# HF_Control.net
KiCad netlist of a schematic drawn in Altium Designer
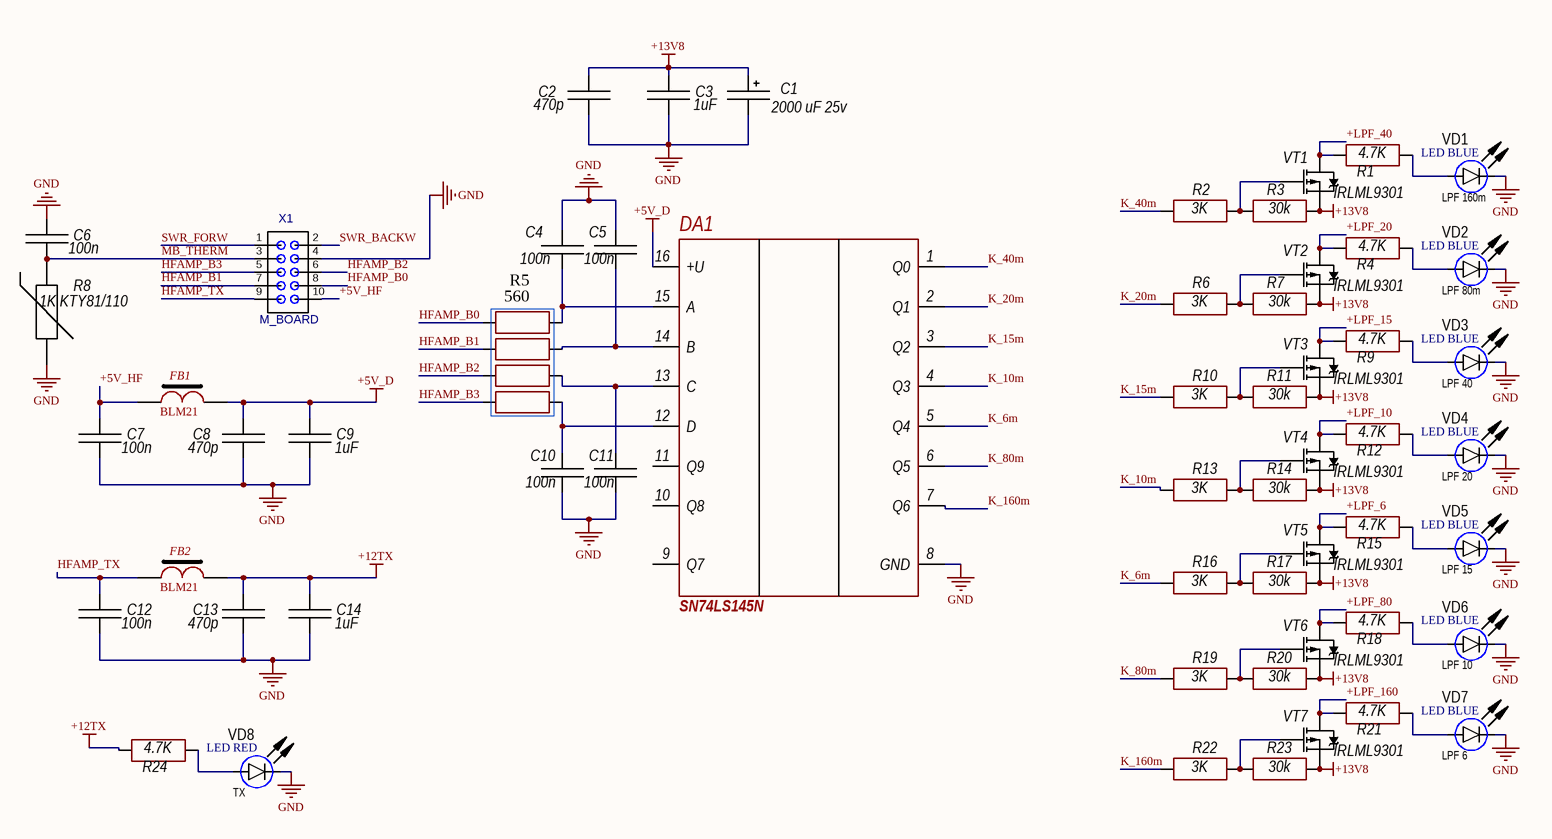
[diagram p0: HF_Control.SchDoc]

(export (version "E")
  (design (tool "Eeschema 10.0.6"))
  (components
    (comp (ref "C1")
      (value "2000 uF 25v")
      (footprint "standard:D13C5H20")
      (libsource (lib "Discrete") (part "AlumCap"))
    )
    (comp (ref "C2")
      (value "470p")
      (footprint "standard:CH0805C")
      (libsource (lib "Discrete") (part "Capacitor"))
    )
    (comp (ref "C3")
      (value "1uF")
      (footprint "standard:CH0805C")
      (libsource (lib "Discrete") (part "Capacitor"))
    )
    (comp (ref "C4")
      (value "100n")
      (footprint "standard:CH0805C")
      (libsource (lib "Discrete") (part "Capacitor"))
    )
    (comp (ref "C5")
      (value "100n")
      (footprint "standard:CH0805C")
      (libsource (lib "Discrete") (part "Capacitor"))
    )
    (comp (ref "C6")
      (value "100n")
      (footprint "standard:CH0805C")
      (libsource (lib "Discrete") (part "Capacitor"))
    )
    (comp (ref "C7")
      (value "100n")
      (footprint "standard:CH0805C")
      (libsource (lib "Discrete") (part "Capacitor"))
    )
    (comp (ref "C8")
      (value "470p")
      (footprint "standard:CH0805C")
      (libsource (lib "Discrete") (part "Capacitor"))
    )
    (comp (ref "C9")
      (value "1uF")
      (footprint "standard:CH0805C")
      (libsource (lib "Discrete") (part "Capacitor"))
    )
    (comp (ref "C10")
      (value "100n")
      (footprint "standard:CH0805C")
      (libsource (lib "Discrete") (part "Capacitor"))
    )
    (comp (ref "C11")
      (value "100n")
      (footprint "standard:CH0805C")
      (libsource (lib "Discrete") (part "Capacitor"))
    )
    (comp (ref "C12")
      (value "100n")
      (footprint "standard:CH0805C")
      (libsource (lib "Discrete") (part "Capacitor"))
    )
    (comp (ref "C13")
      (value "470p")
      (footprint "standard:CH0805C")
      (libsource (lib "Discrete") (part "Capacitor"))
    )
    (comp (ref "C14")
      (value "1uF")
      (footprint "standard:CH0805C")
      (libsource (lib "Discrete") (part "Capacitor"))
    )
    (comp (ref "DA1")
      (value "SN74LS145N")
      (footprint "16-SOP")
      (libsource (lib "Digital") (part "SN74LS145N"))
    )
    (comp (ref "FB1") (value "BLM21") (footprint "CH0805L") (libsource (lib "Discrete") (part "FB-1")))
    (comp (ref "FB2") (value "BLM21") (footprint "CH0805L") (libsource (lib "Discrete") (part "FB-1")))
    (comp (ref "R1")
      (value "4.7K")
      (footprint "standard:CH0805R")
      (libsource (lib "Discrete") (part "Resistor"))
    )
    (comp (ref "R2") (value "3K") (footprint "standard:CH0805R") (libsource (lib "") (part "Resistor_1")))
    (comp (ref "R3")
      (value "30k")
      (footprint "standard:CH0805R")
      (libsource (lib "Discrete") (part "Resistor"))
    )
    (comp (ref "R4")
      (value "4.7K")
      (footprint "standard:CH0805R")
      (libsource (lib "Discrete") (part "Resistor"))
    )
    (comp (ref "R5") (value "560") (footprint "CAT16") (libsource (lib "Discrete") (part "CAT10-0804")))
    (comp (ref "R6") (value "3K") (footprint "standard:CH0805R") (libsource (lib "") (part "Resistor_1")))
    (comp (ref "R7")
      (value "30k")
      (footprint "standard:CH0805R")
      (libsource (lib "Discrete") (part "Resistor"))
    )
    (comp (ref "R8")
      (value "1K KTY81/110")
      (footprint "CON: PBS-2")
      (libsource (lib "Discrete") (part "NTC"))
    )
    (comp (ref "R9")
      (value "4.7K")
      (footprint "standard:CH0805R")
      (libsource (lib "Discrete") (part "Resistor"))
    )
    (comp (ref "R10") (value "3K") (footprint "standard:CH0805R") (libsource (lib "") (part "Resistor_1")))
    (comp (ref "R11")
      (value "30k")
      (footprint "standard:CH0805R")
      (libsource (lib "Discrete") (part "Resistor"))
    )
    (comp (ref "R12")
      (value "4.7K")
      (footprint "standard:CH0805R")
      (libsource (lib "Discrete") (part "Resistor"))
    )
    (comp (ref "R13") (value "3K") (footprint "standard:CH0805R") (libsource (lib "") (part "Resistor_1")))
    (comp (ref "R14")
      (value "30k")
      (footprint "standard:CH0805R")
      (libsource (lib "Discrete") (part "Resistor"))
    )
    (comp (ref "R15")
      (value "4.7K")
      (footprint "standard:CH0805R")
      (libsource (lib "Discrete") (part "Resistor"))
    )
    (comp (ref "R16") (value "3K") (footprint "standard:CH0805R") (libsource (lib "") (part "Resistor_1")))
    (comp (ref "R17")
      (value "30k")
      (footprint "standard:CH0805R")
      (libsource (lib "Discrete") (part "Resistor"))
    )
    (comp (ref "R18")
      (value "4.7K")
      (footprint "standard:CH0805R")
      (libsource (lib "Discrete") (part "Resistor"))
    )
    (comp (ref "R19") (value "3K") (footprint "standard:CH0805R") (libsource (lib "") (part "Resistor_1")))
    (comp (ref "R20")
      (value "30k")
      (footprint "standard:CH0805R")
      (libsource (lib "Discrete") (part "Resistor"))
    )
    (comp (ref "R21")
      (value "4.7K")
      (footprint "standard:CH0805R")
      (libsource (lib "Discrete") (part "Resistor"))
    )
    (comp (ref "R22") (value "3K") (footprint "standard:CH0805R") (libsource (lib "") (part "Resistor_1")))
    (comp (ref "R23")
      (value "30k")
      (footprint "standard:CH0805R")
      (libsource (lib "Discrete") (part "Resistor"))
    )
    (comp (ref "R24")
      (value "4.7K")
      (footprint "standard:CH0805R")
      (libsource (lib "Discrete") (part "Resistor"))
    )
    (comp (ref "VD1")
      (value "LED BLUE")
      (footprint "StandardCase:LED: 0805B")
      (fields
        (field (name "VALUEMANUFACTURERPARTNUMBER") "LED, *, *, *, -55...+150°C")
        (field (name "COLOR") "LPF 160m")
      )
      (libsource (lib "Diode") (part "LED_single"))
    )
    (comp (ref "VD2")
      (value "LED BLUE")
      (footprint "StandardCase:LED: 0805B")
      (fields
        (field (name "VALUEMANUFACTURERPARTNUMBER") "LED, *, *, *, -55...+150°C")
        (field (name "COLOR") "LPF 80m")
      )
      (libsource (lib "Diode") (part "LED_single"))
    )
    (comp (ref "VD3")
      (value "LED BLUE")
      (footprint "StandardCase:LED: 0805B")
      (fields
        (field (name "VALUEMANUFACTURERPARTNUMBER") "LED, *, *, *, -55...+150°C")
        (field (name "COLOR") "LPF 40")
      )
      (libsource (lib "Diode") (part "LED_single"))
    )
    (comp (ref "VD4")
      (value "LED BLUE")
      (footprint "StandardCase:LED: 0805B")
      (fields
        (field (name "VALUEMANUFACTURERPARTNUMBER") "LED, *, *, *, -55...+150°C")
        (field (name "COLOR") "LPF 20")
      )
      (libsource (lib "Diode") (part "LED_single"))
    )
    (comp (ref "VD5")
      (value "LED BLUE")
      (footprint "StandardCase:LED: 0805B")
      (fields
        (field (name "VALUEMANUFACTURERPARTNUMBER") "LED, *, *, *, -55...+150°C")
        (field (name "COLOR") "LPF 15")
      )
      (libsource (lib "Diode") (part "LED_single"))
    )
    (comp (ref "VD6")
      (value "LED BLUE")
      (footprint "StandardCase:LED: 0805B")
      (fields
        (field (name "VALUEMANUFACTURERPARTNUMBER") "LED, *, *, *, -55...+150°C")
        (field (name "COLOR") "LPF 10")
      )
      (libsource (lib "Diode") (part "LED_single"))
    )
    (comp (ref "VD7")
      (value "LED BLUE")
      (footprint "StandardCase:LED: 0805B")
      (fields
        (field (name "VALUEMANUFACTURERPARTNUMBER") "LED, *, *, *, -55...+150°C")
        (field (name "COLOR") "LPF 6")
      )
      (libsource (lib "Diode") (part "LED_single"))
    )
    (comp (ref "VD8")
      (value "LED RED")
      (footprint "StandardCase:LED: 0805R")
      (fields
        (field (name "VALUEMANUFACTURERPARTNUMBER") "LED, *, *, *, -55...+150°C")
        (field (name "COLOR") "TX")
      )
      (libsource (lib "Diode") (part "LED_single"))
    )
    (comp (ref "VT1")
      (value "IRLML9301")
      (footprint "standard:SOT23_132")
      (description "Mosfet")
      (libsource (lib "Transistor") (part "IRLML9301"))
    )
    (comp (ref "VT2")
      (value "IRLML9301")
      (footprint "standard:SOT23_132")
      (description "Mosfet")
      (libsource (lib "Transistor") (part "IRLML9301"))
    )
    (comp (ref "VT3")
      (value "IRLML9301")
      (footprint "standard:SOT23_132")
      (description "Mosfet")
      (libsource (lib "Transistor") (part "IRLML9301"))
    )
    (comp (ref "VT4")
      (value "IRLML9301")
      (footprint "standard:SOT23_132")
      (description "Mosfet")
      (libsource (lib "Transistor") (part "IRLML9301"))
    )
    (comp (ref "VT5")
      (value "IRLML9301")
      (footprint "standard:SOT23_132")
      (description "Mosfet")
      (libsource (lib "Transistor") (part "IRLML9301"))
    )
    (comp (ref "VT6")
      (value "IRLML9301")
      (footprint "standard:SOT23_132")
      (description "Mosfet")
      (libsource (lib "Transistor") (part "IRLML9301"))
    )
    (comp (ref "VT7")
      (value "IRLML9301")
      (footprint "standard:SOT23_132")
      (description "Mosfet")
      (libsource (lib "Transistor") (part "IRLML9301"))
    )
    (comp (ref "X1")
      (value "M_BOARD")
      (footprint "CON: BH-10")
      (description "2*5 Pin")
      (libsource (lib "*") (part "IDC10"))
    )
  )
  (nets
    (net (code "1") (name "+5V_D") (class "Default")
      (node (ref "C8") (pin "1") (pinfunction "1_1") (pintype "power_in"))
      (node (ref "C9") (pin "1") (pinfunction "1_1") (pintype "power_in"))
      (node (ref "DA1") (pin "16") (pinfunction "+U_16") (pintype "passive"))
      (node (ref "FB1") (pin "1") (pinfunction "1_1") (pintype "passive"))
    )
    (net (code "2") (name "+12TX") (class "Default")
      (node (ref "C13") (pin "1") (pinfunction "1_1") (pintype "power_in"))
      (node (ref "C14") (pin "1") (pinfunction "1_1") (pintype "power_in"))
      (node (ref "FB2") (pin "1") (pinfunction "1_1") (pintype "passive"))
      (node (ref "R24") (pin "2") (pinfunction "2_2") (pintype "passive"))
    )
    (net (code "3") (name "+13V8") (class "Default")
      (node (ref "C1") (pin "1") (pinfunction "1_1") (pintype "power_in"))
      (node (ref "C2") (pin "1") (pinfunction "1_1") (pintype "power_in"))
      (node (ref "C3") (pin "1") (pinfunction "1_1") (pintype "power_in"))
      (node (ref "R11") (pin "1") (pinfunction "1_1") (pintype "passive"))
      (node (ref "R14") (pin "1") (pinfunction "1_1") (pintype "passive"))
      (node (ref "R17") (pin "1") (pinfunction "1_1") (pintype "passive"))
      (node (ref "R20") (pin "1") (pinfunction "1_1") (pintype "passive"))
      (node (ref "R23") (pin "1") (pinfunction "1_1") (pintype "passive"))
      (node (ref "R3") (pin "1") (pinfunction "1_1") (pintype "passive"))
      (node (ref "R7") (pin "1") (pinfunction "1_1") (pintype "passive"))
      (node (ref "VT1") (pin "2") (pinfunction "S_2") (pintype "passive"))
      (node (ref "VT2") (pin "2") (pinfunction "S_2") (pintype "passive"))
      (node (ref "VT3") (pin "2") (pinfunction "S_2") (pintype "passive"))
      (node (ref "VT4") (pin "2") (pinfunction "S_2") (pintype "passive"))
      (node (ref "VT5") (pin "2") (pinfunction "S_2") (pintype "passive"))
      (node (ref "VT6") (pin "2") (pinfunction "S_2") (pintype "passive"))
      (node (ref "VT7") (pin "2") (pinfunction "S_2") (pintype "passive"))
    )
    (net (code "4") (name "/+5V_HF") (class "Default")
      (node (ref "C7") (pin "1") (pinfunction "1_1") (pintype "power_in"))
      (node (ref "FB1") (pin "2") (pinfunction "2_2") (pintype "passive"))
      (node (ref "X1") (pin "10") (pinfunction "10_10") (pintype "passive"))
    )
    (net (code "5") (name "/+LPF_6") (class "Default")
      (node (ref "R15") (pin "2") (pinfunction "2_2") (pintype "passive"))
      (node (ref "VT5") (pin "3") (pinfunction "D_3") (pintype "passive"))
    )
    (net (code "6") (name "/+LPF_10") (class "Default")
      (node (ref "R12") (pin "2") (pinfunction "2_2") (pintype "passive"))
      (node (ref "VT4") (pin "3") (pinfunction "D_3") (pintype "passive"))
    )
    (net (code "7") (name "/+LPF_15") (class "Default")
      (node (ref "R9") (pin "2") (pinfunction "2_2") (pintype "passive"))
      (node (ref "VT3") (pin "3") (pinfunction "D_3") (pintype "passive"))
    )
    (net (code "8") (name "/+LPF_20") (class "Default")
      (node (ref "R4") (pin "2") (pinfunction "2_2") (pintype "passive"))
      (node (ref "VT2") (pin "3") (pinfunction "D_3") (pintype "passive"))
    )
    (net (code "9") (name "/+LPF_40") (class "Default")
      (node (ref "R1") (pin "2") (pinfunction "2_2") (pintype "passive"))
      (node (ref "VT1") (pin "3") (pinfunction "D_3") (pintype "passive"))
    )
    (net (code "10") (name "/+LPF_80") (class "Default")
      (node (ref "R18") (pin "2") (pinfunction "2_2") (pintype "passive"))
      (node (ref "VT6") (pin "3") (pinfunction "D_3") (pintype "passive"))
    )
    (net (code "11") (name "/+LPF_160") (class "Default")
      (node (ref "R21") (pin "2") (pinfunction "2_2") (pintype "passive"))
      (node (ref "VT7") (pin "3") (pinfunction "D_3") (pintype "passive"))
    )
    (net (code "12") (name "/HFAMP_B0") (class "Default")
      (node (ref "R5") (pin "1") (pinfunction "1_1") (pintype "passive"))
      (node (ref "X1") (pin "8") (pinfunction "8_8") (pintype "passive"))
    )
    (net (code "13") (name "/HFAMP_B1") (class "Default")
      (node (ref "R5") (pin "2") (pinfunction "2_2") (pintype "passive"))
      (node (ref "X1") (pin "7") (pinfunction "7_7") (pintype "passive"))
    )
    (net (code "14") (name "/HFAMP_B2") (class "Default")
      (node (ref "R5") (pin "3") (pinfunction "3_3") (pintype "passive"))
      (node (ref "X1") (pin "6") (pinfunction "6_6") (pintype "passive"))
    )
    (net (code "15") (name "/HFAMP_B3") (class "Default")
      (node (ref "R5") (pin "4") (pinfunction "4_4") (pintype "passive"))
      (node (ref "X1") (pin "5") (pinfunction "5_5") (pintype "passive"))
    )
    (net (code "16") (name "/HFAMP_TX") (class "Default")
      (node (ref "C12") (pin "1") (pinfunction "1_1") (pintype "power_in"))
      (node (ref "FB2") (pin "2") (pinfunction "2_2") (pintype "passive"))
      (node (ref "X1") (pin "9") (pinfunction "9_9") (pintype "passive"))
    )
    (net (code "17") (name "/K_6m") (class "Default")
      (node (ref "DA1") (pin "5") (pinfunction "Q4_5") (pintype "passive"))
      (node (ref "R16") (pin "2") (pinfunction "2_2") (pintype "passive"))
    )
    (net (code "18") (name "/K_10m") (class "Default")
      (node (ref "DA1") (pin "4") (pinfunction "Q3_4") (pintype "passive"))
      (node (ref "R13") (pin "2") (pinfunction "2_2") (pintype "passive"))
    )
    (net (code "19") (name "/K_15m") (class "Default")
      (node (ref "DA1") (pin "3") (pinfunction "Q2_3") (pintype "passive"))
      (node (ref "R10") (pin "2") (pinfunction "2_2") (pintype "passive"))
    )
    (net (code "20") (name "/K_20m") (class "Default")
      (node (ref "DA1") (pin "2") (pinfunction "Q1_2") (pintype "passive"))
      (node (ref "R6") (pin "2") (pinfunction "2_2") (pintype "passive"))
    )
    (net (code "21") (name "/K_40m") (class "Default")
      (node (ref "DA1") (pin "1") (pinfunction "Q0_1") (pintype "passive"))
      (node (ref "R2") (pin "2") (pinfunction "2_2") (pintype "passive"))
    )
    (net (code "22") (name "/K_80m") (class "Default")
      (node (ref "DA1") (pin "6") (pinfunction "Q5_6") (pintype "passive"))
      (node (ref "R19") (pin "2") (pinfunction "2_2") (pintype "passive"))
    )
    (net (code "23") (name "/K_160m") (class "Default")
      (node (ref "DA1") (pin "7") (pinfunction "Q6_7") (pintype "passive"))
      (node (ref "R22") (pin "2") (pinfunction "2_2") (pintype "passive"))
    )
    (net (code "24") (name "/MB_THERM") (class "Default")
      (node (ref "C6") (pin "2") (pinfunction "2_2") (pintype "power_in"))
      (node (ref "R8") (pin "2") (pinfunction "2_2") (pintype "passive"))
      (node (ref "X1") (pin "3") (pinfunction "3_3") (pintype "passive"))
    )
    (net (code "25") (name "/SWR_BACKW") (class "Default")
      (node (ref "X1") (pin "2") (pinfunction "2_2") (pintype "passive"))
    )
    (net (code "26") (name "/SWR_FORW") (class "Default")
      (node (ref "X1") (pin "1") (pinfunction "1_1") (pintype "passive"))
    )
    (net (code "27") (name "GND") (class "Default")
      (node (ref "C1") (pin "2") (pinfunction "2_2") (pintype "power_in"))
      (node (ref "C10") (pin "2") (pinfunction "2_2") (pintype "power_in"))
      (node (ref "C11") (pin "2") (pinfunction "2_2") (pintype "power_in"))
      (node (ref "C12") (pin "2") (pinfunction "2_2") (pintype "power_in"))
      (node (ref "C13") (pin "2") (pinfunction "2_2") (pintype "power_in"))
      (node (ref "C14") (pin "2") (pinfunction "2_2") (pintype "power_in"))
      (node (ref "C2") (pin "2") (pinfunction "2_2") (pintype "power_in"))
      (node (ref "C3") (pin "2") (pinfunction "2_2") (pintype "power_in"))
      (node (ref "C4") (pin "1") (pinfunction "1_1") (pintype "power_in"))
      (node (ref "C5") (pin "1") (pinfunction "1_1") (pintype "power_in"))
      (node (ref "C6") (pin "1") (pinfunction "1_1") (pintype "power_in"))
      (node (ref "C7") (pin "2") (pinfunction "2_2") (pintype "power_in"))
      (node (ref "C8") (pin "2") (pinfunction "2_2") (pintype "power_in"))
      (node (ref "C9") (pin "2") (pinfunction "2_2") (pintype "power_in"))
      (node (ref "DA1") (pin "8") (pinfunction "GND_8") (pintype "passive"))
      (node (ref "R8") (pin "1") (pinfunction "1_1") (pintype "passive"))
      (node (ref "VD1") (pin "2") (pinfunction "C_2") (pintype "passive"))
      (node (ref "VD2") (pin "2") (pinfunction "C_2") (pintype "passive"))
      (node (ref "VD3") (pin "2") (pinfunction "C_2") (pintype "passive"))
      (node (ref "VD4") (pin "2") (pinfunction "C_2") (pintype "passive"))
      (node (ref "VD5") (pin "2") (pinfunction "C_2") (pintype "passive"))
      (node (ref "VD6") (pin "2") (pinfunction "C_2") (pintype "passive"))
      (node (ref "VD7") (pin "2") (pinfunction "C_2") (pintype "passive"))
      (node (ref "VD8") (pin "2") (pinfunction "C_2") (pintype "passive"))
      (node (ref "X1") (pin "4") (pinfunction "4_4") (pintype "passive"))
    )
    (net (code "28") (name "Net-(DA1-A)") (class "Default")
      (node (ref "C4") (pin "2") (pinfunction "2_2") (pintype "power_in"))
      (node (ref "DA1") (pin "15") (pinfunction "A_15") (pintype "passive"))
      (node (ref "R5") (pin "5") (pinfunction "5_5") (pintype "passive"))
    )
    (net (code "29") (name "Net-(DA1-B)") (class "Default")
      (node (ref "C5") (pin "2") (pinfunction "2_2") (pintype "power_in"))
      (node (ref "DA1") (pin "14") (pinfunction "B_14") (pintype "passive"))
      (node (ref "R5") (pin "6") (pinfunction "6_6") (pintype "passive"))
    )
    (net (code "30") (name "Net-(DA1-C)") (class "Default")
      (node (ref "C11") (pin "1") (pinfunction "1_1") (pintype "power_in"))
      (node (ref "DA1") (pin "13") (pinfunction "C_13") (pintype "passive"))
      (node (ref "R5") (pin "7") (pinfunction "7_7") (pintype "passive"))
    )
    (net (code "31") (name "Net-(DA1-D)") (class "Default")
      (node (ref "C10") (pin "1") (pinfunction "1_1") (pintype "power_in"))
      (node (ref "DA1") (pin "12") (pinfunction "D_12") (pintype "passive"))
      (node (ref "R5") (pin "8") (pinfunction "8_8") (pintype "passive"))
    )
    (net (code "32") (name "Net-(VD1-A)") (class "Default")
      (node (ref "R1") (pin "1") (pinfunction "1_1") (pintype "passive"))
      (node (ref "VD1") (pin "1") (pinfunction "A_1") (pintype "passive"))
    )
    (net (code "33") (name "Net-(VD2-A)") (class "Default")
      (node (ref "R4") (pin "1") (pinfunction "1_1") (pintype "passive"))
      (node (ref "VD2") (pin "1") (pinfunction "A_1") (pintype "passive"))
    )
    (net (code "34") (name "Net-(VD3-A)") (class "Default")
      (node (ref "R9") (pin "1") (pinfunction "1_1") (pintype "passive"))
      (node (ref "VD3") (pin "1") (pinfunction "A_1") (pintype "passive"))
    )
    (net (code "35") (name "Net-(VD4-A)") (class "Default")
      (node (ref "R12") (pin "1") (pinfunction "1_1") (pintype "passive"))
      (node (ref "VD4") (pin "1") (pinfunction "A_1") (pintype "passive"))
    )
    (net (code "36") (name "Net-(VD5-A)") (class "Default")
      (node (ref "R15") (pin "1") (pinfunction "1_1") (pintype "passive"))
      (node (ref "VD5") (pin "1") (pinfunction "A_1") (pintype "passive"))
    )
    (net (code "37") (name "Net-(VD6-A)") (class "Default")
      (node (ref "R18") (pin "1") (pinfunction "1_1") (pintype "passive"))
      (node (ref "VD6") (pin "1") (pinfunction "A_1") (pintype "passive"))
    )
    (net (code "38") (name "Net-(VD7-A)") (class "Default")
      (node (ref "R21") (pin "1") (pinfunction "1_1") (pintype "passive"))
      (node (ref "VD7") (pin "1") (pinfunction "A_1") (pintype "passive"))
    )
    (net (code "39") (name "Net-(VD8-A)") (class "Default")
      (node (ref "R24") (pin "1") (pinfunction "1_1") (pintype "passive"))
      (node (ref "VD8") (pin "1") (pinfunction "A_1") (pintype "passive"))
    )
    (net (code "40") (name "Net-(VT1-G)") (class "Default")
      (node (ref "R2") (pin "1") (pinfunction "1_1") (pintype "passive"))
      (node (ref "R3") (pin "2") (pinfunction "2_2") (pintype "passive"))
      (node (ref "VT1") (pin "1") (pinfunction "G_1") (pintype "passive"))
    )
    (net (code "41") (name "Net-(VT2-G)") (class "Default")
      (node (ref "R6") (pin "1") (pinfunction "1_1") (pintype "passive"))
      (node (ref "R7") (pin "2") (pinfunction "2_2") (pintype "passive"))
      (node (ref "VT2") (pin "1") (pinfunction "G_1") (pintype "passive"))
    )
    (net (code "42") (name "Net-(VT3-G)") (class "Default")
      (node (ref "R10") (pin "1") (pinfunction "1_1") (pintype "passive"))
      (node (ref "R11") (pin "2") (pinfunction "2_2") (pintype "passive"))
      (node (ref "VT3") (pin "1") (pinfunction "G_1") (pintype "passive"))
    )
    (net (code "43") (name "Net-(VT4-G)") (class "Default")
      (node (ref "R13") (pin "1") (pinfunction "1_1") (pintype "passive"))
      (node (ref "R14") (pin "2") (pinfunction "2_2") (pintype "passive"))
      (node (ref "VT4") (pin "1") (pinfunction "G_1") (pintype "passive"))
    )
    (net (code "44") (name "Net-(VT5-G)") (class "Default")
      (node (ref "R16") (pin "1") (pinfunction "1_1") (pintype "passive"))
      (node (ref "R17") (pin "2") (pinfunction "2_2") (pintype "passive"))
      (node (ref "VT5") (pin "1") (pinfunction "G_1") (pintype "passive"))
    )
    (net (code "45") (name "Net-(VT6-G)") (class "Default")
      (node (ref "R19") (pin "1") (pinfunction "1_1") (pintype "passive"))
      (node (ref "R20") (pin "2") (pinfunction "2_2") (pintype "passive"))
      (node (ref "VT6") (pin "1") (pinfunction "G_1") (pintype "passive"))
    )
    (net (code "46") (name "Net-(VT7-G)") (class "Default")
      (node (ref "R22") (pin "1") (pinfunction "1_1") (pintype "passive"))
      (node (ref "R23") (pin "2") (pinfunction "2_2") (pintype "passive"))
      (node (ref "VT7") (pin "1") (pinfunction "G_1") (pintype "passive"))
    )
    (net (code "47") (name "unconnected-(DA1-Q7-Pad9)") (class "Default")
      (node (ref "DA1") (pin "9") (pinfunction "Q7_9") (pintype "passive"))
    )
    (net (code "48") (name "unconnected-(DA1-Q8-Pad10)") (class "Default")
      (node (ref "DA1") (pin "10") (pinfunction "Q8_10") (pintype "passive"))
    )
    (net (code "49") (name "unconnected-(DA1-Q9-Pad11)") (class "Default")
      (node (ref "DA1") (pin "11") (pinfunction "Q9_11") (pintype "passive"))
    )
  )
)
